# Access_System_F.net
KiCad netlist of a schematic drawn in Altium Designer
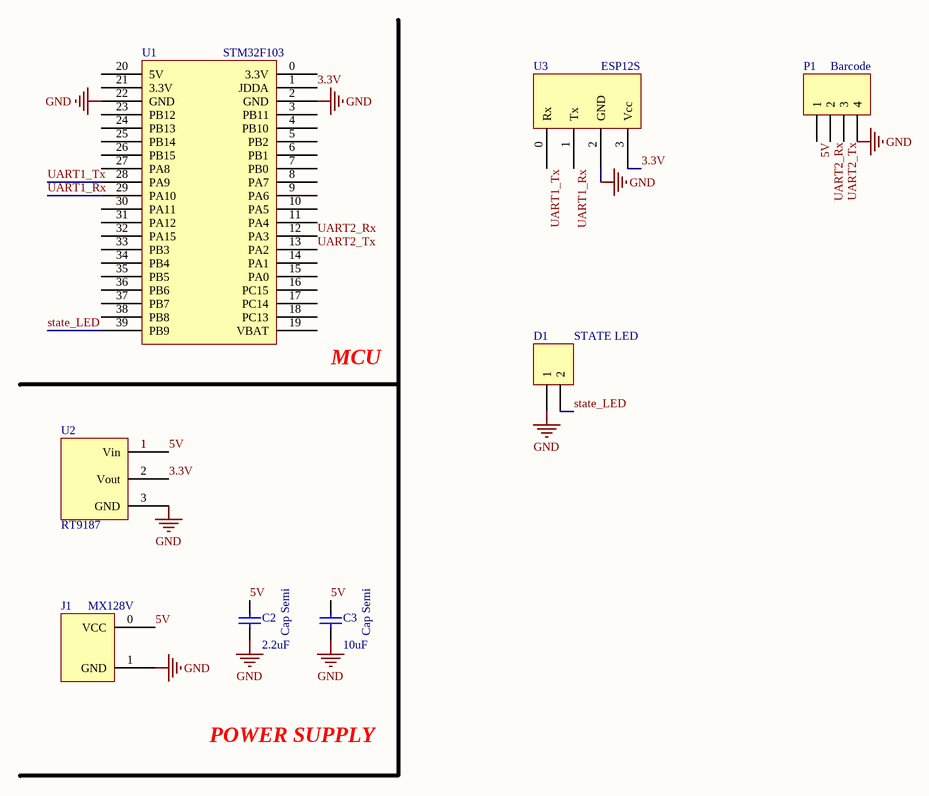
[diagram p0: Access_System_F.SchDoc]

(export (version "E")
  (design (tool "Eeschema 10.0.6"))
  (components
    (comp (ref "C2")
      (value "Cap Semi")
      (footprint "1608[0603]")
      (description "Capacitor (Semiconductor SIM Model)")
      (fields (field (name "ALTIUM_VALUE") "2.2uF") (field (name "PUBLISHER") "Altium Limited"))
      (libsource (lib "Miscellaneous Devices") (part "Cap Semi"))
    )
    (comp (ref "C3")
      (value "Cap Semi")
      (footprint "1608[0603]")
      (description "Capacitor (Semiconductor SIM Model)")
      (fields (field (name "ALTIUM_VALUE") "10uF") (field (name "PUBLISHER") "Altium Limited"))
      (libsource (lib "Miscellaneous Devices") (part "Cap Semi"))
    )
    (comp (ref "D1")
      (value "STATE LED")
      (footprint "HDR1X2")
      (description "Header, 2-Pin")
      (fields (field (name "PUBLISHER") "Altium Limited"))
      (libsource (lib "Miscellaneous Connectors") (part "Header 2"))
    )
    (comp (ref "J1") (value "MX128V") (footprint "MX128V") (libsource (lib "access_LIB") (part "MX128V")))
    (comp (ref "P1")
      (value "Barcode")
      (footprint "HDR1X4")
      (description "Header, 4-Pin")
      (fields (field (name "PUBLISHER") "Altium Limited"))
      (libsource (lib "Miscellaneous Connectors") (part "Header 4"))
    )
    (comp (ref "U1")
      (value "STM32F103")
      (footprint "STM32F103")
      (libsource (lib "access_LIB") (part "STM32F103"))
    )
    (comp (ref "U2") (value "RT9187") (footprint "RT9187") (libsource (lib "access_LIB") (part "RT9187")))
    (comp (ref "U3") (value "ESP12S") (footprint "ESP12S") (libsource (lib "access_LIB") (part "ESP12S")))
  )
  (nets
    (net (code "1") (name "/3.3V") (class "Default")
      (node (ref "U1") (pin "1") (pinfunction "JDDA_1") (pintype "passive"))
      (node (ref "U2") (pin "2") (pinfunction "Vout_2") (pintype "passive"))
      (node (ref "U3") (pin "3") (pinfunction "Vcc_3") (pintype "passive"))
    )
    (net (code "2") (name "/5V") (class "Default")
      (node (ref "C2") (pin "2") (pinfunction "2_2") (pintype "passive"))
      (node (ref "C3") (pin "2") (pinfunction "2_2") (pintype "passive"))
      (node (ref "J1") (pin "0") (pinfunction "VCC_0") (pintype "passive"))
      (node (ref "P1") (pin "1") (pinfunction "1_1") (pintype "passive"))
      (node (ref "U2") (pin "1") (pinfunction "Vin_1") (pintype "passive"))
    )
    (net (code "3") (name "/UART1_Rx") (class "Default")
      (node (ref "U1") (pin "29") (pinfunction "PA10_29") (pintype "passive"))
      (node (ref "U3") (pin "1") (pinfunction "Tx_1") (pintype "passive"))
    )
    (net (code "4") (name "/UART1_Tx") (class "Default")
      (node (ref "U1") (pin "28") (pinfunction "PA9_28") (pintype "passive"))
      (node (ref "U3") (pin "0") (pinfunction "Rx_0") (pintype "passive"))
    )
    (net (code "5") (name "/UART2_Rx") (class "Default")
      (node (ref "P1") (pin "2") (pinfunction "2_2") (pintype "passive"))
      (node (ref "U1") (pin "12") (pinfunction "PA3_12") (pintype "passive"))
    )
    (net (code "6") (name "/UART2_Tx") (class "Default")
      (node (ref "P1") (pin "3") (pinfunction "3_3") (pintype "passive"))
      (node (ref "U1") (pin "13") (pinfunction "PA2_13") (pintype "passive"))
    )
    (net (code "7") (name "/state_LED") (class "Default")
      (node (ref "D1") (pin "2") (pinfunction "2_2") (pintype "passive"))
      (node (ref "U1") (pin "39") (pinfunction "PB9_39") (pintype "passive"))
    )
    (net (code "8") (name "GND") (class "Default")
      (node (ref "C2") (pin "1") (pinfunction "1_1") (pintype "passive"))
      (node (ref "C3") (pin "1") (pinfunction "1_1") (pintype "passive"))
      (node (ref "D1") (pin "1") (pinfunction "1_1") (pintype "passive"))
      (node (ref "J1") (pin "1") (pinfunction "GND_1") (pintype "passive"))
      (node (ref "P1") (pin "4") (pinfunction "4_4") (pintype "passive"))
      (node (ref "U1") (pin "2") (pinfunction "GND_2") (pintype "passive"))
      (node (ref "U1") (pin "22") (pinfunction "GND_22") (pintype "passive"))
      (node (ref "U2") (pin "3") (pinfunction "GND_3") (pintype "passive"))
      (node (ref "U3") (pin "2") (pinfunction "GND_2") (pintype "passive"))
    )
    (net (code "9") (name "unconnected-(U1-3.3V-Pad0)") (class "Default")
      (node (ref "U1") (pin "0") (pinfunction "3.3V_0") (pintype "passive"))
    )
    (net (code "10") (name "unconnected-(U1-3.3V-Pad21)") (class "Default")
      (node (ref "U1") (pin "21") (pinfunction "3.3V_21") (pintype "passive"))
    )
    (net (code "11") (name "unconnected-(U1-5V-Pad20)") (class "Default")
      (node (ref "U1") (pin "20") (pinfunction "5V_20") (pintype "passive"))
    )
    (net (code "12") (name "unconnected-(U1-PA0-Pad15)") (class "Default")
      (node (ref "U1") (pin "15") (pinfunction "PA0_15") (pintype "passive"))
    )
    (net (code "13") (name "unconnected-(U1-PA1-Pad14)") (class "Default")
      (node (ref "U1") (pin "14") (pinfunction "PA1_14") (pintype "passive"))
    )
    (net (code "14") (name "unconnected-(U1-PA4-Pad11)") (class "Default")
      (node (ref "U1") (pin "11") (pinfunction "PA4_11") (pintype "passive"))
    )
    (net (code "15") (name "unconnected-(U1-PA5-Pad10)") (class "Default")
      (node (ref "U1") (pin "10") (pinfunction "PA5_10") (pintype "passive"))
    )
    (net (code "16") (name "unconnected-(U1-PA6-Pad9)") (class "Default")
      (node (ref "U1") (pin "9") (pinfunction "PA6_9") (pintype "passive"))
    )
    (net (code "17") (name "unconnected-(U1-PA7-Pad8)") (class "Default")
      (node (ref "U1") (pin "8") (pinfunction "PA7_8") (pintype "passive"))
    )
    (net (code "18") (name "unconnected-(U1-PA8-Pad27)") (class "Default")
      (node (ref "U1") (pin "27") (pinfunction "PA8_27") (pintype "passive"))
    )
    (net (code "19") (name "unconnected-(U1-PA11-Pad30)") (class "Default")
      (node (ref "U1") (pin "30") (pinfunction "PA11_30") (pintype "passive"))
    )
    (net (code "20") (name "unconnected-(U1-PA12-Pad31)") (class "Default")
      (node (ref "U1") (pin "31") (pinfunction "PA12_31") (pintype "passive"))
    )
    (net (code "21") (name "unconnected-(U1-PA15-Pad32)") (class "Default")
      (node (ref "U1") (pin "32") (pinfunction "PA15_32") (pintype "passive"))
    )
    (net (code "22") (name "unconnected-(U1-PB0-Pad7)") (class "Default")
      (node (ref "U1") (pin "7") (pinfunction "PB0_7") (pintype "passive"))
    )
    (net (code "23") (name "unconnected-(U1-PB1-Pad6)") (class "Default")
      (node (ref "U1") (pin "6") (pinfunction "PB1_6") (pintype "passive"))
    )
    (net (code "24") (name "unconnected-(U1-PB2-Pad5)") (class "Default")
      (node (ref "U1") (pin "5") (pinfunction "PB2_5") (pintype "passive"))
    )
    (net (code "25") (name "unconnected-(U1-PB3-Pad33)") (class "Default")
      (node (ref "U1") (pin "33") (pinfunction "PB3_33") (pintype "passive"))
    )
    (net (code "26") (name "unconnected-(U1-PB4-Pad34)") (class "Default")
      (node (ref "U1") (pin "34") (pinfunction "PB4_34") (pintype "passive"))
    )
    (net (code "27") (name "unconnected-(U1-PB5-Pad35)") (class "Default")
      (node (ref "U1") (pin "35") (pinfunction "PB5_35") (pintype "passive"))
    )
    (net (code "28") (name "unconnected-(U1-PB6-Pad36)") (class "Default")
      (node (ref "U1") (pin "36") (pinfunction "PB6_36") (pintype "passive"))
    )
    (net (code "29") (name "unconnected-(U1-PB7-Pad37)") (class "Default")
      (node (ref "U1") (pin "37") (pinfunction "PB7_37") (pintype "passive"))
    )
    (net (code "30") (name "unconnected-(U1-PB8-Pad38)") (class "Default")
      (node (ref "U1") (pin "38") (pinfunction "PB8_38") (pintype "passive"))
    )
    (net (code "31") (name "unconnected-(U1-PB10-Pad4)") (class "Default")
      (node (ref "U1") (pin "4") (pinfunction "PB10_4") (pintype "passive"))
    )
    (net (code "32") (name "unconnected-(U1-PB11-Pad3)") (class "Default")
      (node (ref "U1") (pin "3") (pinfunction "PB11_3") (pintype "passive"))
    )
    (net (code "33") (name "unconnected-(U1-PB12-Pad23)") (class "Default")
      (node (ref "U1") (pin "23") (pinfunction "PB12_23") (pintype "passive"))
    )
    (net (code "34") (name "unconnected-(U1-PB13-Pad24)") (class "Default")
      (node (ref "U1") (pin "24") (pinfunction "PB13_24") (pintype "passive"))
    )
    (net (code "35") (name "unconnected-(U1-PB14-Pad25)") (class "Default")
      (node (ref "U1") (pin "25") (pinfunction "PB14_25") (pintype "passive"))
    )
    (net (code "36") (name "unconnected-(U1-PB15-Pad26)") (class "Default")
      (node (ref "U1") (pin "26") (pinfunction "PB15_26") (pintype "passive"))
    )
    (net (code "37") (name "unconnected-(U1-PC13-Pad18)") (class "Default")
      (node (ref "U1") (pin "18") (pinfunction "PC13_18") (pintype "passive"))
    )
    (net (code "38") (name "unconnected-(U1-PC14-Pad17)") (class "Default")
      (node (ref "U1") (pin "17") (pinfunction "PC14_17") (pintype "passive"))
    )
    (net (code "39") (name "unconnected-(U1-PC15-Pad16)") (class "Default")
      (node (ref "U1") (pin "16") (pinfunction "PC15_16") (pintype "passive"))
    )
    (net (code "40") (name "unconnected-(U1-VBAT-Pad19)") (class "Default")
      (node (ref "U1") (pin "19") (pinfunction "VBAT_19") (pintype "passive"))
    )
  )
)
